# Sheet1.net
KiCad netlist of a schematic drawn in Altium Designer
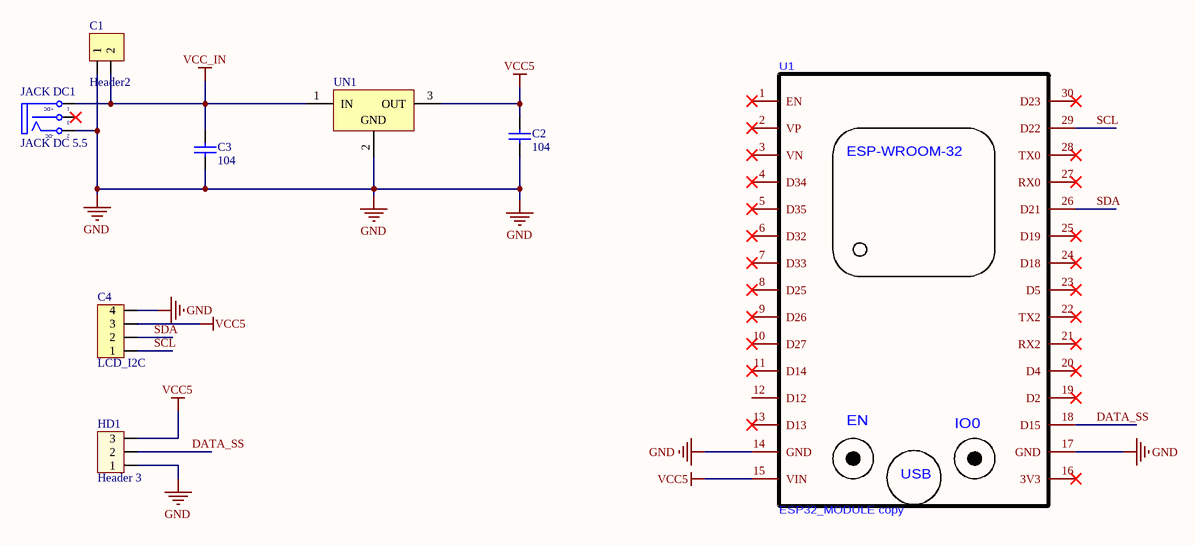
[diagram p0: Sheet1.SchDoc]

(export (version "E")
  (design (tool "Eeschema 10.0.6"))
  (components
    (comp (ref "C1")
      (value "Header2")
      (footprint "Header2")
      (description "Header IDC, 2 x 1 Pin Vertical 2.54mm Pitch (Non-Boxed, Male)")
      (fields
        (field (name "MANUFACTURER") "Würth Elektronik eiSos GmbH")
        (field (name "PARTNO") "613002143121")
        (field (name "CREATED BY") "Karrer Zheng")
      )
      (libsource (lib "myLib_v1") (part "Header2"))
    )
    (comp (ref "C2")
      (value "104")
      (footprint "tu gom")
      (description "Cắm")
      (libsource (lib "Altium_Lib_by_KhueNguyenCreator") (part "Tu gom 104 50V"))
    )
    (comp (ref "C3")
      (value "104")
      (footprint "tu gom")
      (description "Cắm")
      (libsource (lib "Altium_Lib_by_KhueNguyenCreator") (part "Tu gom 104 50V"))
    )
    (comp (ref "C4")
      (value "LCD_I2C")
      (footprint "Header4")
      (description "Header IDC, 4 x 1 Pin Vertical 2.54mm Pitch (Non-Boxed, Male)")
      (fields
        (field (name "MANUFACTURER") "Würth Elektronik eiSos GmbH")
        (field (name "PARTNO") "613002143121")
        (field (name "CREATED BY") "Karrer Zheng")
      )
      (libsource (lib "myLib_v1") (part "Header4"))
    )
    (comp (ref "HD1")
      (value "Header 3")
      (footprint "HED3")
      (description "Header 3 (Green)")
      (libsource (lib "syhaunguyen") (part "Hed3"))
    )
    (comp (ref "JACK DC1")
      (value "JACK DC 5.5")
      (footprint "JACK DC 5.5")
      (libsource (lib "Altium_Lib_by_KhueNguyenCreator") (part "JACK DC 5.5"))
    )
    (comp (ref "U1")
      (value "ESP32_MODULE copy")
      (footprint "ESP32-WIFIMODULE-FOOTPRINT")
      (libsource (lib "myLib_v1") (part "ESP32_MODULE copy"))
    )
    (comp (ref "UN1")
      (value "L78M05CP")
      (footprint "QTO-220H2")
      (description "Positive Voltage Regulator")
      (fields (field (name "PUBLISHER") "Altium Limited"))
      (libsource (lib "syhaunguyen") (part "L78M05CP"))
    )
  )
  (nets
    (net (code "1") (name "/DATA_SS") (class "Default")
      (node (ref "HD1") (pin "2") (pinfunction "2_2") (pintype "passive"))
      (node (ref "U1") (pin "18") (pinfunction "D15_18") (pintype "passive"))
    )
    (net (code "2") (name "/SCL") (class "Default")
      (node (ref "C4") (pin "1") (pinfunction "1_1") (pintype "passive"))
      (node (ref "U1") (pin "29") (pinfunction "D22_29") (pintype "passive"))
    )
    (net (code "3") (name "/SDA") (class "Default")
      (node (ref "C4") (pin "2") (pinfunction "2_2") (pintype "passive"))
      (node (ref "U1") (pin "26") (pinfunction "D21_26") (pintype "passive"))
    )
    (net (code "4") (name "GND") (class "Default")
      (node (ref "C1") (pin "1") (pinfunction "1_1") (pintype "passive"))
      (node (ref "C2") (pin "2") (pinfunction "2_2") (pintype "passive"))
      (node (ref "C3") (pin "2") (pinfunction "2_2") (pintype "passive"))
      (node (ref "C4") (pin "4") (pinfunction "4_4") (pintype "passive"))
      (node (ref "HD1") (pin "1") (pinfunction "1_1") (pintype "passive"))
      (node (ref "JACK DC1") (pin "2") (pinfunction "TN_2") (pintype "passive"))
      (node (ref "U1") (pin "14") (pinfunction "GND_14") (pintype "passive"))
      (node (ref "U1") (pin "17") (pinfunction "GND_17") (pintype "passive"))
      (node (ref "UN1") (pin "2") (pinfunction "GND_2") (pintype "power_in"))
    )
    (net (code "5") (name "VCC5") (class "Default")
      (node (ref "C2") (pin "1") (pinfunction "1_1") (pintype "passive"))
      (node (ref "C4") (pin "3") (pinfunction "3_3") (pintype "passive"))
      (node (ref "HD1") (pin "3") (pinfunction "3_3") (pintype "passive"))
      (node (ref "U1") (pin "15") (pinfunction "VIN_15") (pintype "passive"))
      (node (ref "UN1") (pin "3") (pinfunction "OUT_3") (pintype "power_in"))
    )
    (net (code "6") (name "VCC_IN") (class "Default")
      (node (ref "C1") (pin "2") (pinfunction "2_2") (pintype "passive"))
      (node (ref "C3") (pin "1") (pinfunction "1_1") (pintype "passive"))
      (node (ref "JACK DC1") (pin "1") (pinfunction "T_1") (pintype "passive"))
      (node (ref "UN1") (pin "1") (pinfunction "IN_1") (pintype "power_in"))
    )
    (net (code "7") (name "unconnected-(JACK DC1-S-Pad3)") (class "Default")
      (node (ref "JACK DC1") (pin "3") (pinfunction "S_3") (pintype "power_in+no_connect"))
    )
    (net (code "8") (name "unconnected-(U1-3V3-Pad16)") (class "Default")
      (node (ref "U1") (pin "16") (pinfunction "3V3_16") (pintype "passive+no_connect"))
    )
    (net (code "9") (name "unconnected-(U1-D2-Pad19)") (class "Default")
      (node (ref "U1") (pin "19") (pinfunction "D2_19") (pintype "passive+no_connect"))
    )
    (net (code "10") (name "unconnected-(U1-D4-Pad20)") (class "Default")
      (node (ref "U1") (pin "20") (pinfunction "D4_20") (pintype "passive+no_connect"))
    )
    (net (code "11") (name "unconnected-(U1-D5-Pad23)") (class "Default")
      (node (ref "U1") (pin "23") (pinfunction "D5_23") (pintype "passive+no_connect"))
    )
    (net (code "12") (name "unconnected-(U1-D12-Pad12)") (class "Default")
      (node (ref "U1") (pin "12") (pinfunction "D12_12") (pintype "passive"))
    )
    (net (code "13") (name "unconnected-(U1-D13-Pad13)") (class "Default")
      (node (ref "U1") (pin "13") (pinfunction "D13_13") (pintype "passive+no_connect"))
    )
    (net (code "14") (name "unconnected-(U1-D14-Pad11)") (class "Default")
      (node (ref "U1") (pin "11") (pinfunction "D14_11") (pintype "passive+no_connect"))
    )
    (net (code "15") (name "unconnected-(U1-D18-Pad24)") (class "Default")
      (node (ref "U1") (pin "24") (pinfunction "D18_24") (pintype "passive+no_connect"))
    )
    (net (code "16") (name "unconnected-(U1-D19-Pad25)") (class "Default")
      (node (ref "U1") (pin "25") (pinfunction "D19_25") (pintype "passive+no_connect"))
    )
    (net (code "17") (name "unconnected-(U1-D23-Pad30)") (class "Default")
      (node (ref "U1") (pin "30") (pinfunction "D23_30") (pintype "passive+no_connect"))
    )
    (net (code "18") (name "unconnected-(U1-D25-Pad8)") (class "Default")
      (node (ref "U1") (pin "8") (pinfunction "D25_8") (pintype "passive+no_connect"))
    )
    (net (code "19") (name "unconnected-(U1-D26-Pad9)") (class "Default")
      (node (ref "U1") (pin "9") (pinfunction "D26_9") (pintype "passive+no_connect"))
    )
    (net (code "20") (name "unconnected-(U1-D27-Pad10)") (class "Default")
      (node (ref "U1") (pin "10") (pinfunction "D27_10") (pintype "passive+no_connect"))
    )
    (net (code "21") (name "unconnected-(U1-D32-Pad6)") (class "Default")
      (node (ref "U1") (pin "6") (pinfunction "D32_6") (pintype "passive+no_connect"))
    )
    (net (code "22") (name "unconnected-(U1-D33-Pad7)") (class "Default")
      (node (ref "U1") (pin "7") (pinfunction "D33_7") (pintype "passive+no_connect"))
    )
    (net (code "23") (name "unconnected-(U1-D34-Pad4)") (class "Default")
      (node (ref "U1") (pin "4") (pinfunction "D34_4") (pintype "passive+no_connect"))
    )
    (net (code "24") (name "unconnected-(U1-D35-Pad5)") (class "Default")
      (node (ref "U1") (pin "5") (pinfunction "D35_5") (pintype "passive+no_connect"))
    )
    (net (code "25") (name "unconnected-(U1-EN-Pad1)") (class "Default")
      (node (ref "U1") (pin "1") (pinfunction "EN_1") (pintype "passive+no_connect"))
    )
    (net (code "26") (name "unconnected-(U1-RX0-Pad27)") (class "Default")
      (node (ref "U1") (pin "27") (pinfunction "RX0_27") (pintype "passive+no_connect"))
    )
    (net (code "27") (name "unconnected-(U1-RX2-Pad21)") (class "Default")
      (node (ref "U1") (pin "21") (pinfunction "RX2_21") (pintype "passive+no_connect"))
    )
    (net (code "28") (name "unconnected-(U1-TX0-Pad28)") (class "Default")
      (node (ref "U1") (pin "28") (pinfunction "TX0_28") (pintype "passive+no_connect"))
    )
    (net (code "29") (name "unconnected-(U1-TX2-Pad22)") (class "Default")
      (node (ref "U1") (pin "22") (pinfunction "TX2_22") (pintype "passive+no_connect"))
    )
    (net (code "30") (name "unconnected-(U1-VN-Pad3)") (class "Default")
      (node (ref "U1") (pin "3") (pinfunction "VN_3") (pintype "passive+no_connect"))
    )
    (net (code "31") (name "unconnected-(U1-VP-Pad2)") (class "Default")
      (node (ref "U1") (pin "2") (pinfunction "VP_2") (pintype "passive+no_connect"))
    )
  )
)
